# CON_SD_HIROSE_609_0003_5.net
KiCad netlist of a schematic drawn in Altium Designer
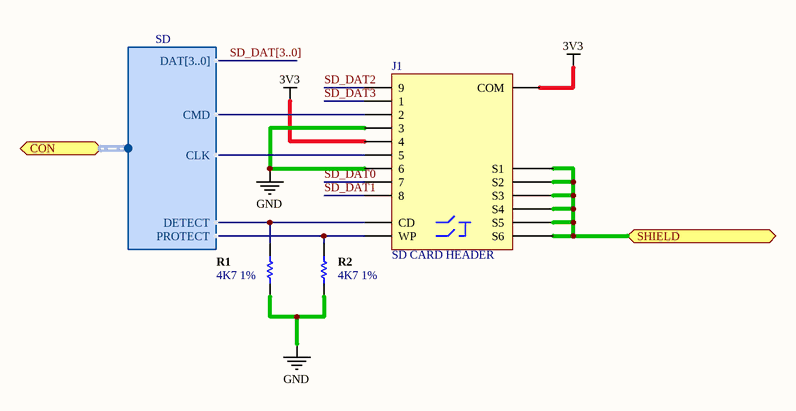
[diagram p0: CON_SD_HIROSE_609_0003_5.SchDoc]

(export (version "E")
  (design (tool "Eeschema 10.0.6"))
  (components
    (comp (ref "J1")
      (value "SD CARD HEADER")
      (footprint "SD_CARD_HRS_609_0003_5")
      (description "Secure Digital Card Socket")
      (libsource (lib "altium-import") (part "root_0_CON-SDCARD_"))
    )
    (comp (ref "R1")
      (value "4K7 1%")
      (footprint "RESC1005-STAR")
      (description "Resistor, 4K7 1% 0402 (1005)")
      (fields (field (name "TOLERANCE") "1 %"))
      (libsource (lib "altium-import") (part "root_2_RES_"))
    )
    (comp (ref "R2")
      (value "4K7 1%")
      (footprint "RESC1005-STAR")
      (description "Resistor, 4K7 1% 0402 (1005)")
      (fields (field (name "TOLERANCE") "1 %"))
      (libsource (lib "altium-import") (part "root_2_RES_"))
    )
  )
  (nets
    (net (code "2") (name "/CLK") (class "Default")
      (node (ref "J1") (pin "5") (pinfunction "5_5") (pintype "passive"))
    )
    (net (code "3") (name "/CMD") (class "Default")
      (node (ref "J1") (pin "2") (pinfunction "2_2") (pintype "passive"))
    )
    (net (code "5") (name "/DETECT") (class "Default")
      (node (ref "J1") (pin "CD") (pinfunction "CD_CD") (pintype "passive"))
      (node (ref "R1") (pin "2") (pinfunction "2_2") (pintype "passive"))
    )
    (net (code "6") (name "/PROTECT") (class "Default")
      (node (ref "J1") (pin "WP") (pinfunction "WP_WP") (pintype "passive"))
      (node (ref "R2") (pin "2") (pinfunction "2_2") (pintype "passive"))
    )
    (net (code "7") (name "/SD_DAT0") (class "Default")
      (node (ref "J1") (pin "7") (pinfunction "7_7") (pintype "passive"))
    )
    (net (code "8") (name "/SD_DAT1") (class "Default")
      (node (ref "J1") (pin "8") (pinfunction "8_8") (pintype "passive"))
    )
    (net (code "9") (name "/SD_DAT2") (class "Default")
      (node (ref "J1") (pin "9") (pinfunction "9_9") (pintype "passive"))
    )
    (net (code "10") (name "/SD_DAT3") (class "Default")
      (node (ref "J1") (pin "1") (pinfunction "1_1") (pintype "passive"))
    )
    (net (code "11") (name "/SHIELD") (class "Default")
      (node (ref "J1") (pin "S1") (pinfunction "S1_S1") (pintype "passive"))
      (node (ref "J1") (pin "S2") (pinfunction "S2_S2") (pintype "passive"))
      (node (ref "J1") (pin "S3") (pinfunction "S3_S3") (pintype "passive"))
      (node (ref "J1") (pin "S4") (pinfunction "S4_S4") (pintype "passive"))
      (node (ref "J1") (pin "S5") (pinfunction "S5_S5") (pintype "passive"))
      (node (ref "J1") (pin "S6") (pinfunction "S6_S6") (pintype "passive"))
    )
    (net (code "13") (name "3V3") (class "Default")
      (node (ref "J1") (pin "4") (pinfunction "4_4") (pintype "passive"))
      (node (ref "J1") (pin "COM") (pinfunction "COM_COM") (pintype "passive"))
    )
    (net (code "14") (name "GND") (class "Default")
      (node (ref "J1") (pin "3") (pinfunction "3_3") (pintype "passive"))
      (node (ref "J1") (pin "6") (pinfunction "6_6") (pintype "passive"))
      (node (ref "R1") (pin "1") (pinfunction "1_1") (pintype "passive"))
      (node (ref "R2") (pin "1") (pinfunction "1_1") (pintype "passive"))
    )
  )
)
